# CELL_BALANCE.net
KiCad netlist of a schematic drawn in Altium Designer
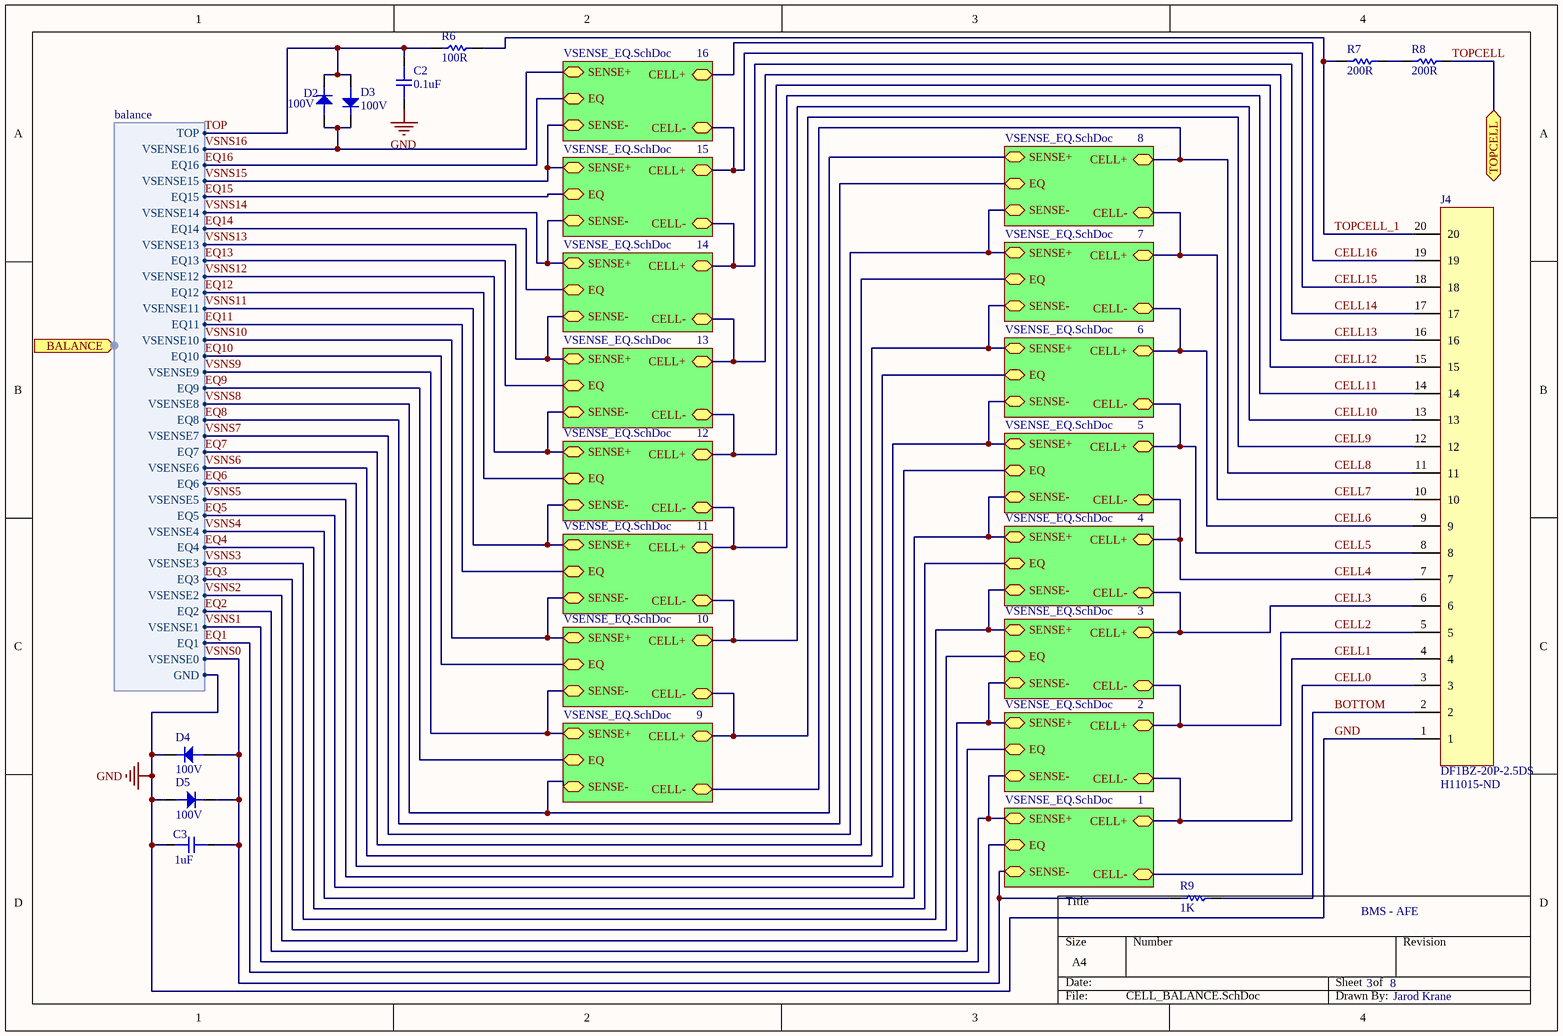
[diagram p0: CELL_BALANCE.SchDoc]

(export (version "E")
  (design (tool "Eeschema 10.0.6"))
  (components
    (comp (ref "C2")
      (value "0.1uF")
      (footprint "1210 cap")
      (description "CAP CER 0.1UF 250V X7R 1210")
      (fields
        (field (name "MANUFACTURER") "KEMET")
        (field (name "MANUFACTURER PART NUMBER") "C1210C104KARACTU")
      )
      (libsource (lib "parts") (part "C1210C104KARACTU"))
    )
    (comp (ref "C3")
      (value "1uF")
      (footprint "0603 CAP - duplicate")
      (description "CAP CER 1UF 16V X7R 0603")
      (fields
        (field (name "MANUFACTURER") "TDK")
        (field (name "MANUFACTURER PART NUMBER") "C1608X7R1C105K080AC")
      )
      (libsource (lib "parts") (part "C1608X7R1C105K080AC"))
    )
    (comp (ref "D2")
      (value "100V")
      (footprint "DIODE BtoB")
      (description "DIODE GEN PURP 100V 300MA SOD123")
      (fields (field (name "MANUFACTURER") "Diodes") (field (name "MANUFACTURER PART NUMBER") "1N4148W-7-F"))
      (libsource (lib "parts") (part "1N4148W-7-F"))
    )
    (comp (ref "D3")
      (value "100V")
      (footprint "DIODE BtoB")
      (description "DIODE GEN PURP 100V 300MA SOD123")
      (fields (field (name "MANUFACTURER") "Diodes") (field (name "MANUFACTURER PART NUMBER") "1N4148W-7-F"))
      (libsource (lib "parts") (part "1N4148W-7-F"))
    )
    (comp (ref "D4")
      (value "100V")
      (footprint "DIODE BtoB")
      (description "DIODE GEN PURP 100V 300MA SOD123")
      (fields (field (name "MANUFACTURER") "Diodes") (field (name "MANUFACTURER PART NUMBER") "1N4148W-7-F"))
      (libsource (lib "parts") (part "1N4148W-7-F"))
    )
    (comp (ref "D5")
      (value "100V")
      (footprint "DIODE BtoB")
      (description "DIODE GEN PURP 100V 300MA SOD123")
      (fields (field (name "MANUFACTURER") "Diodes") (field (name "MANUFACTURER PART NUMBER") "1N4148W-7-F"))
      (libsource (lib "parts") (part "1N4148W-7-F"))
    )
    (comp (ref "J4")
      (value "DF1BZ-20P-2.5DS")
      (footprint "PCBComponent_1")
      (description "CONN HEADER 20POS 2.5MM R/A TIN")
      (fields (field (name "MANUFACTURER") "Hirose") (field (name "SUPPLIER PART NUMBER 1") "H11015-ND"))
      (libsource (lib "parts") (part "DF1BZ-20P-2.5DS"))
    )
    (comp (ref "R6")
      (value "100R")
      (footprint "1206 RES")
      (description "RES SMD 100 OHM 1% 1/4W 1206")
      (fields
        (field (name "MANUFACTURER") "Panasonic")
        (field (name "MANUFACTURER PART NUMBER") "ERJ-8ENF1000V")
      )
      (libsource (lib "parts") (part "ERJ-8ENF1000V"))
    )
    (comp (ref "R7")
      (value "200R")
      (footprint "2512 RES")
      (description "RES SMD 200 OHM 5% 1W 2512")
      (fields
        (field (name "MANUFACTURER") "Vishay Dale")
        (field (name "MANUFACTURER PART NUMBER") "CRCW2512200RJNEG")
      )
      (libsource (lib "parts") (part "CRCW2512200RJNEG"))
    )
    (comp (ref "R8")
      (value "200R")
      (footprint "2512 RES")
      (description "RES SMD 200 OHM 5% 1W 2512")
      (fields
        (field (name "MANUFACTURER") "Vishay Dale")
        (field (name "MANUFACTURER PART NUMBER") "CRCW2512200RJNEG")
      )
      (libsource (lib "parts") (part "CRCW2512200RJNEG"))
    )
    (comp (ref "R9")
      (value "1K")
      (footprint "0603 RES")
      (description "RES SMD 1K OHM 1% 1/10W 0603")
      (fields
        (field (name "MANUFACTURER") "Vishay Dale")
        (field (name "MANUFACTURER PART NUMBER") "CRCW06031K00FKEA")
      )
      (libsource (lib "parts") (part "CRCW06031K00FKEA"))
    )
  )
  (nets
    (net (code "2") (name "/BOTTOM") (class "Default")
      (node (ref "J4") (pin "2") (pinfunction "2_2") (pintype "passive"))
      (node (ref "R9") (pin "2") (pinfunction "2_2") (pintype "passive"))
    )
    (net (code "3") (name "/CELL0") (class "Default")
      (node (ref "J4") (pin "3") (pinfunction "3_3") (pintype "passive"))
    )
    (net (code "4") (name "/CELL1") (class "Default")
      (node (ref "J4") (pin "4") (pinfunction "4_4") (pintype "passive"))
    )
    (net (code "5") (name "/CELL2") (class "Default")
      (node (ref "J4") (pin "5") (pinfunction "5_5") (pintype "passive"))
    )
    (net (code "6") (name "/CELL3") (class "Default")
      (node (ref "J4") (pin "6") (pinfunction "6_6") (pintype "passive"))
    )
    (net (code "7") (name "/CELL4") (class "Default")
      (node (ref "J4") (pin "7") (pinfunction "7_7") (pintype "passive"))
    )
    (net (code "8") (name "/CELL5") (class "Default")
      (node (ref "J4") (pin "8") (pinfunction "8_8") (pintype "passive"))
    )
    (net (code "9") (name "/CELL6") (class "Default")
      (node (ref "J4") (pin "9") (pinfunction "9_9") (pintype "passive"))
    )
    (net (code "10") (name "/CELL7") (class "Default")
      (node (ref "J4") (pin "10") (pinfunction "10_10") (pintype "passive"))
    )
    (net (code "11") (name "/CELL8") (class "Default")
      (node (ref "J4") (pin "11") (pinfunction "11_11") (pintype "passive"))
    )
    (net (code "12") (name "/CELL9") (class "Default")
      (node (ref "J4") (pin "12") (pinfunction "12_12") (pintype "passive"))
    )
    (net (code "13") (name "/CELL10") (class "Default")
      (node (ref "J4") (pin "13") (pinfunction "13_13") (pintype "passive"))
    )
    (net (code "14") (name "/CELL11") (class "Default")
      (node (ref "J4") (pin "14") (pinfunction "14_14") (pintype "passive"))
    )
    (net (code "15") (name "/CELL12") (class "Default")
      (node (ref "J4") (pin "15") (pinfunction "15_15") (pintype "passive"))
    )
    (net (code "16") (name "/CELL13") (class "Default")
      (node (ref "J4") (pin "16") (pinfunction "16_16") (pintype "passive"))
    )
    (net (code "17") (name "/CELL14") (class "Default")
      (node (ref "J4") (pin "17") (pinfunction "17_17") (pintype "passive"))
    )
    (net (code "18") (name "/CELL15") (class "Default")
      (node (ref "J4") (pin "18") (pinfunction "18_18") (pintype "passive"))
    )
    (net (code "19") (name "/CELL16") (class "Default")
      (node (ref "J4") (pin "19") (pinfunction "19_19") (pintype "passive"))
    )
    (net (code "37") (name "/TOPCELL") (class "Default")
      (node (ref "R8") (pin "2") (pinfunction "2_2") (pintype "passive"))
    )
    (net (code "38") (name "/TOPCELL_1") (class "Default")
      (node (ref "J4") (pin "20") (pinfunction "20_20") (pintype "passive"))
      (node (ref "R6") (pin "2") (pinfunction "2_2") (pintype "passive"))
      (node (ref "R7") (pin "1") (pinfunction "1_1") (pintype "passive"))
    )
    (net (code "39") (name "/VSNS0") (class "Default")
      (node (ref "C3") (pin "2") (pinfunction "2_2") (pintype "passive"))
      (node (ref "D4") (pin "1") (pinfunction "1_1") (pintype "passive"))
      (node (ref "D5") (pin "2") (pinfunction "2_2") (pintype "passive"))
      (node (ref "R9") (pin "1") (pinfunction "1_1") (pintype "passive"))
    )
    (net (code "55") (name "/VSNS16") (class "Default")
      (node (ref "D2") (pin "1") (pinfunction "1_1") (pintype "passive"))
      (node (ref "D3") (pin "2") (pinfunction "2_2") (pintype "passive"))
    )
    (net (code "57") (name "GND") (class "Default")
      (node (ref "C2") (pin "1") (pinfunction "1_1") (pintype "passive"))
      (node (ref "C3") (pin "1") (pinfunction "1_1") (pintype "passive"))
      (node (ref "D4") (pin "2") (pinfunction "2_2") (pintype "passive"))
      (node (ref "D5") (pin "1") (pinfunction "1_1") (pintype "passive"))
      (node (ref "J4") (pin "1") (pinfunction "1_1") (pintype "passive"))
    )
    (net (code "58") (name "Net-(C2-Pad2)") (class "Default")
      (node (ref "C2") (pin "2") (pinfunction "2_2") (pintype "passive"))
      (node (ref "D2") (pin "2") (pinfunction "2_2") (pintype "passive"))
      (node (ref "D3") (pin "1") (pinfunction "1_1") (pintype "passive"))
      (node (ref "R6") (pin "1") (pinfunction "1_1") (pintype "passive"))
    )
    (net (code "59") (name "Net-(R7-Pad2)") (class "Default")
      (node (ref "R7") (pin "2") (pinfunction "2_2") (pintype "passive"))
      (node (ref "R8") (pin "1") (pinfunction "1_1") (pintype "passive"))
    )
  )
)
